# helicopter.net
KiCad netlist of a schematic drawn in EAGLE
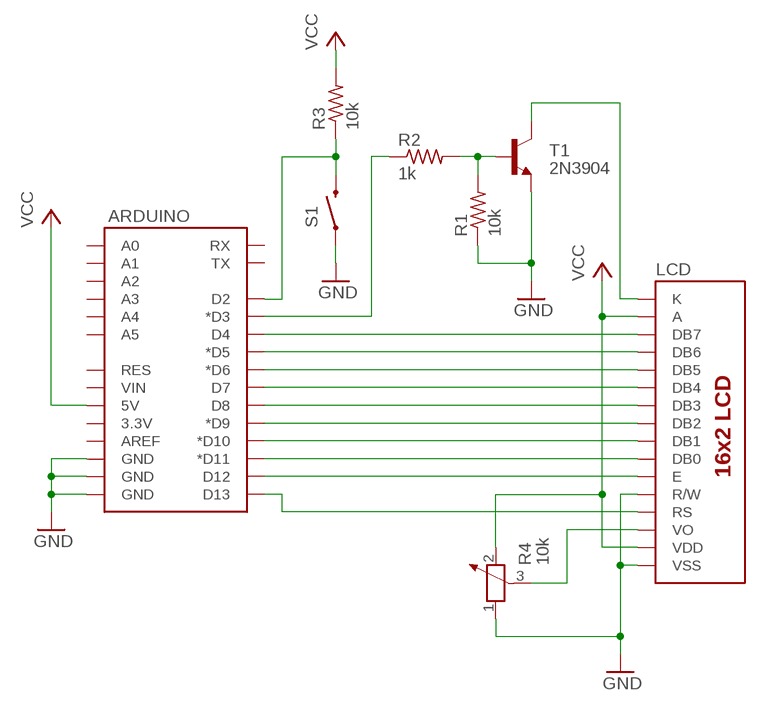
[diagram p0: schematic, sheet 1]

(export (version "E")
  (design (tool "Eeschema 10.0.6"))
  (components
    (comp (ref "ARDUINO")
      (value "ARDUINO_SHIELDLABEL")
      (footprint "eagle-import:DUEMILANOVE_SHIELD")
      (libsource (lib "eagle-import") (part "ARDUINO_SHIELDLABEL"))
    )
    (comp (ref "LCD")
      (value "LCD-16X2NOHOLES")
      (footprint "eagle-import:LCD-16X2_NOHOLES")
      (libsource (lib "eagle-import") (part "LCD-16X2NOHOLES"))
    )
    (comp (ref "R1")
      (value "10k")
      (footprint "eagle-import:0207_10")
      (libsource (lib "eagle-import") (part "R-US_0207/10"))
    )
    (comp (ref "R2")
      (value "1k")
      (footprint "eagle-import:0207_10")
      (libsource (lib "eagle-import") (part "R-US_0207/10"))
    )
    (comp (ref "R3")
      (value "10k")
      (footprint "eagle-import:0207_10")
      (libsource (lib "eagle-import") (part "R-US_0207/10"))
    )
    (comp (ref "R4")
      (value "10k")
      (footprint "eagle-import:PT-10")
      (libsource (lib "eagle-import") (part "POTENTIOMETER_PT-10"))
    )
    (comp (ref "S1")
      (value "SWITCH-MOMENTARY-2PTH")
      (footprint "eagle-import:TACTILE-PTH")
      (libsource (lib "eagle-import") (part "SWITCH-MOMENTARY-2PTH"))
    )
    (comp (ref "T1")
      (value "2N3904")
      (footprint "eagle-import:TO92")
      (libsource (lib "eagle-import") (part "2N3904"))
    )
  )
  (nets
    (net (code "1") (name "GND") (class "Default")
      (node (ref "ARDUINO") (pin "GND@0") (pinfunction "GND_GND@0") (pintype "bidirectional"))
      (node (ref "ARDUINO") (pin "GND@1") (pinfunction "GND_GND@1") (pintype "bidirectional"))
      (node (ref "ARDUINO") (pin "GND@2") (pinfunction "GND_GND@2") (pintype "bidirectional"))
      (node (ref "LCD") (pin "1") (pinfunction "VSS_1") (pintype "power_in"))
      (node (ref "LCD") (pin "5") (pinfunction "R/W_5") (pintype "input"))
      (node (ref "R1") (pin "1") (pinfunction "1_1") (pintype "passive"))
      (node (ref "R4") (pin "1") (pinfunction "1_1") (pintype "passive"))
      (node (ref "S1") (pin "1") (pinfunction "1_1") (pintype "passive"))
      (node (ref "T1") (pin "3") (pinfunction "E_3") (pintype "passive"))
    )
    (net (code "2") (name "Net-(ARDUINO-*D3)") (class "Default")
      (node (ref "ARDUINO") (pin "D3") (pinfunction "*D3_D3") (pintype "bidirectional"))
      (node (ref "R2") (pin "1") (pinfunction "1_1") (pintype "passive"))
    )
    (net (code "3") (name "Net-(ARDUINO-*D5)") (class "Default")
      (node (ref "ARDUINO") (pin "D5") (pinfunction "*D5_D5") (pintype "bidirectional"))
      (node (ref "LCD") (pin "13") (pinfunction "DB6_13") (pintype "bidirectional"))
    )
    (net (code "4") (name "Net-(ARDUINO-*D6)") (class "Default")
      (node (ref "ARDUINO") (pin "D6") (pinfunction "*D6_D6") (pintype "bidirectional"))
      (node (ref "LCD") (pin "12") (pinfunction "DB5_12") (pintype "bidirectional"))
    )
    (net (code "5") (name "Net-(ARDUINO-*D9)") (class "Default")
      (node (ref "ARDUINO") (pin "D9") (pinfunction "*D9_D9") (pintype "bidirectional"))
      (node (ref "LCD") (pin "9") (pinfunction "DB2_9") (pintype "bidirectional"))
    )
    (net (code "6") (name "Net-(ARDUINO-*D10)") (class "Default")
      (node (ref "ARDUINO") (pin "D10") (pinfunction "*D10_D10") (pintype "bidirectional"))
      (node (ref "LCD") (pin "8") (pinfunction "DB1_8") (pintype "bidirectional"))
    )
    (net (code "7") (name "Net-(ARDUINO-*D11)") (class "Default")
      (node (ref "ARDUINO") (pin "D11") (pinfunction "*D11_D11") (pintype "bidirectional"))
      (node (ref "LCD") (pin "7") (pinfunction "DB0_7") (pintype "bidirectional"))
    )
    (net (code "8") (name "Net-(LCD-DB3)") (class "Default")
      (node (ref "ARDUINO") (pin "D8") (pinfunction "D8_D8") (pintype "bidirectional"))
      (node (ref "LCD") (pin "10") (pinfunction "DB3_10") (pintype "bidirectional"))
    )
    (net (code "9") (name "Net-(LCD-DB4)") (class "Default")
      (node (ref "ARDUINO") (pin "D7") (pinfunction "D7_D7") (pintype "bidirectional"))
      (node (ref "LCD") (pin "11") (pinfunction "DB4_11") (pintype "bidirectional"))
    )
    (net (code "10") (name "Net-(LCD-DB7)") (class "Default")
      (node (ref "ARDUINO") (pin "D4") (pinfunction "D4_D4") (pintype "bidirectional"))
      (node (ref "LCD") (pin "14") (pinfunction "DB7_14") (pintype "bidirectional"))
    )
    (net (code "11") (name "Net-(LCD-E)") (class "Default")
      (node (ref "ARDUINO") (pin "D12") (pinfunction "D12_D12") (pintype "bidirectional"))
      (node (ref "LCD") (pin "6") (pinfunction "E_6") (pintype "input"))
    )
    (net (code "12") (name "Net-(LCD-K)") (class "Default")
      (node (ref "LCD") (pin "16") (pinfunction "K_16") (pintype "power_in"))
      (node (ref "T1") (pin "1") (pinfunction "C_1") (pintype "passive"))
    )
    (net (code "13") (name "Net-(LCD-RS)") (class "Default")
      (node (ref "ARDUINO") (pin "D13") (pinfunction "D13_D13") (pintype "bidirectional"))
      (node (ref "LCD") (pin "4") (pinfunction "RS_4") (pintype "input"))
    )
    (net (code "14") (name "Net-(LCD-VO)") (class "Default")
      (node (ref "LCD") (pin "3") (pinfunction "VO_3") (pintype "bidirectional"))
      (node (ref "R4") (pin "3") (pinfunction "3_3") (pintype "passive"))
    )
    (net (code "15") (name "Net-(S1-2)") (class "Default")
      (node (ref "ARDUINO") (pin "D2") (pinfunction "D2_D2") (pintype "bidirectional"))
      (node (ref "R3") (pin "1") (pinfunction "1_1") (pintype "passive"))
      (node (ref "S1") (pin "3") (pinfunction "2_3") (pintype "passive"))
    )
    (net (code "16") (name "Net-(T1-B)") (class "Default")
      (node (ref "R1") (pin "2") (pinfunction "2_2") (pintype "passive"))
      (node (ref "R2") (pin "2") (pinfunction "2_2") (pintype "passive"))
      (node (ref "T1") (pin "2") (pinfunction "B_2") (pintype "passive"))
    )
    (net (code "17") (name "VCC") (class "Default")
      (node (ref "ARDUINO") (pin "5V") (pinfunction "5V_5V") (pintype "bidirectional"))
      (node (ref "LCD") (pin "15") (pinfunction "A_15") (pintype "power_in"))
      (node (ref "LCD") (pin "2") (pinfunction "VDD_2") (pintype "power_in"))
      (node (ref "R3") (pin "2") (pinfunction "2_2") (pintype "passive"))
      (node (ref "R4") (pin "2") (pinfunction "2_2") (pintype "passive"))
    )
    (net (code "18") (name "unconnected-(ARDUINO-Pad3.3V)") (class "Default")
      (node (ref "ARDUINO") (pin "3.3V") (pinfunction "3.3V_3.3V") (pintype "bidirectional"))
    )
    (net (code "19") (name "unconnected-(ARDUINO-PadA0)") (class "Default")
      (node (ref "ARDUINO") (pin "A0") (pinfunction "A0_A0") (pintype "bidirectional"))
    )
    (net (code "20") (name "unconnected-(ARDUINO-PadA1)") (class "Default")
      (node (ref "ARDUINO") (pin "A1") (pinfunction "A1_A1") (pintype "bidirectional"))
    )
    (net (code "21") (name "unconnected-(ARDUINO-PadA2)") (class "Default")
      (node (ref "ARDUINO") (pin "A2") (pinfunction "A2_A2") (pintype "bidirectional"))
    )
    (net (code "22") (name "unconnected-(ARDUINO-PadA3)") (class "Default")
      (node (ref "ARDUINO") (pin "A3") (pinfunction "A3_A3") (pintype "bidirectional"))
    )
    (net (code "23") (name "unconnected-(ARDUINO-PadA4)") (class "Default")
      (node (ref "ARDUINO") (pin "A4") (pinfunction "A4_A4") (pintype "bidirectional"))
    )
    (net (code "24") (name "unconnected-(ARDUINO-PadA5)") (class "Default")
      (node (ref "ARDUINO") (pin "A5") (pinfunction "A5_A5") (pintype "bidirectional"))
    )
    (net (code "25") (name "unconnected-(ARDUINO-PadAREF)") (class "Default")
      (node (ref "ARDUINO") (pin "AREF") (pinfunction "AREF_AREF") (pintype "bidirectional"))
    )
    (net (code "26") (name "unconnected-(ARDUINO-PadRES)") (class "Default")
      (node (ref "ARDUINO") (pin "RES") (pinfunction "RES_RES") (pintype "bidirectional"))
    )
    (net (code "27") (name "unconnected-(ARDUINO-PadRX)") (class "Default")
      (node (ref "ARDUINO") (pin "RX") (pinfunction "RX_RX") (pintype "bidirectional"))
    )
    (net (code "28") (name "unconnected-(ARDUINO-PadTX)") (class "Default")
      (node (ref "ARDUINO") (pin "TX") (pinfunction "TX_TX") (pintype "bidirectional"))
    )
    (net (code "29") (name "unconnected-(ARDUINO-PadVIN)") (class "Default")
      (node (ref "ARDUINO") (pin "VIN") (pinfunction "VIN_VIN") (pintype "bidirectional"))
    )
  )
)
